# Vision_Impaired_Arduino_Board.net
KiCad netlist of a schematic drawn in EAGLE
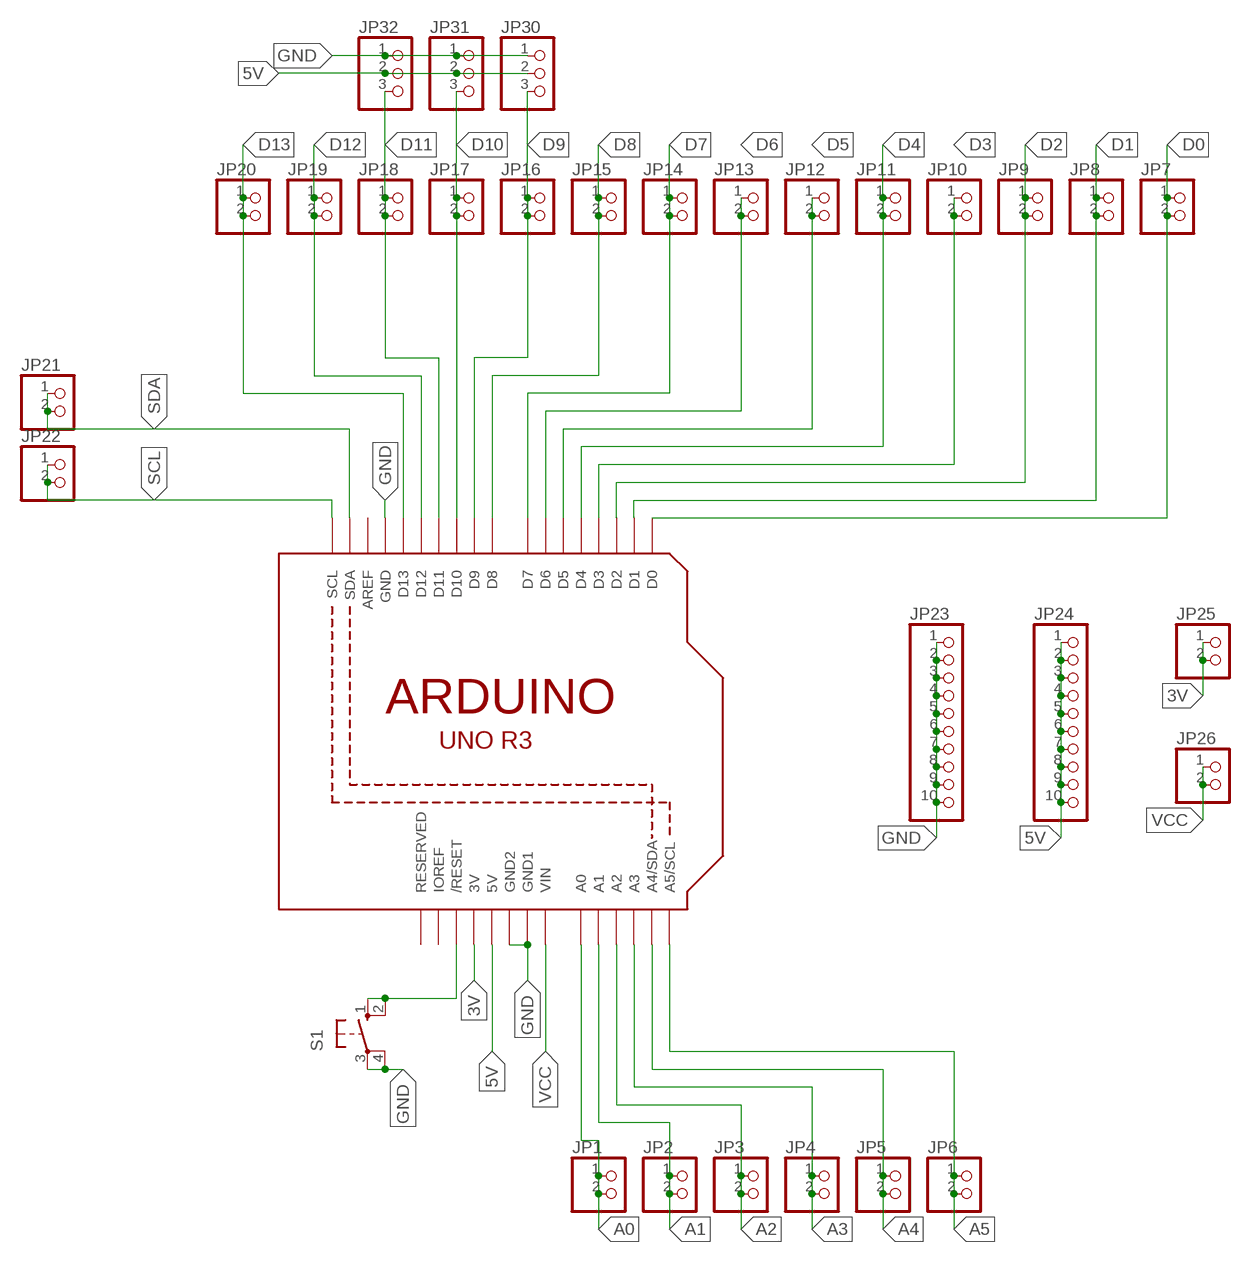
[diagram p0: schematic, sheet 1]

(export (version "E")
  (design (tool "Eeschema 10.0.6"))
  (components
    (comp (ref "JP1")
      (value "PINHD-1X2")
      (footprint "eagle-import:1X02")
      (libsource (lib "eagle-import") (part "PINHD-1X2"))
    )
    (comp (ref "JP2")
      (value "PINHD-1X2")
      (footprint "eagle-import:1X02")
      (libsource (lib "eagle-import") (part "PINHD-1X2"))
    )
    (comp (ref "JP3")
      (value "PINHD-1X2")
      (footprint "eagle-import:1X02")
      (libsource (lib "eagle-import") (part "PINHD-1X2"))
    )
    (comp (ref "JP4")
      (value "PINHD-1X2")
      (footprint "eagle-import:1X02")
      (libsource (lib "eagle-import") (part "PINHD-1X2"))
    )
    (comp (ref "JP5")
      (value "PINHD-1X2")
      (footprint "eagle-import:1X02")
      (libsource (lib "eagle-import") (part "PINHD-1X2"))
    )
    (comp (ref "JP6")
      (value "PINHD-1X2")
      (footprint "eagle-import:1X02")
      (libsource (lib "eagle-import") (part "PINHD-1X2"))
    )
    (comp (ref "JP7")
      (value "PINHD-1X2")
      (footprint "eagle-import:1X02")
      (libsource (lib "eagle-import") (part "PINHD-1X2"))
    )
    (comp (ref "JP8")
      (value "PINHD-1X2")
      (footprint "eagle-import:1X02")
      (libsource (lib "eagle-import") (part "PINHD-1X2"))
    )
    (comp (ref "JP9")
      (value "PINHD-1X2")
      (footprint "eagle-import:1X02")
      (libsource (lib "eagle-import") (part "PINHD-1X2"))
    )
    (comp (ref "JP10")
      (value "PINHD-1X2")
      (footprint "eagle-import:1X02")
      (libsource (lib "eagle-import") (part "PINHD-1X2"))
    )
    (comp (ref "JP11")
      (value "PINHD-1X2")
      (footprint "eagle-import:1X02")
      (libsource (lib "eagle-import") (part "PINHD-1X2"))
    )
    (comp (ref "JP12")
      (value "PINHD-1X2")
      (footprint "eagle-import:1X02")
      (libsource (lib "eagle-import") (part "PINHD-1X2"))
    )
    (comp (ref "JP13")
      (value "PINHD-1X2")
      (footprint "eagle-import:1X02")
      (libsource (lib "eagle-import") (part "PINHD-1X2"))
    )
    (comp (ref "JP14")
      (value "PINHD-1X2")
      (footprint "eagle-import:1X02")
      (libsource (lib "eagle-import") (part "PINHD-1X2"))
    )
    (comp (ref "JP15")
      (value "PINHD-1X2")
      (footprint "eagle-import:1X02")
      (libsource (lib "eagle-import") (part "PINHD-1X2"))
    )
    (comp (ref "JP16")
      (value "PINHD-1X2")
      (footprint "eagle-import:1X02")
      (libsource (lib "eagle-import") (part "PINHD-1X2"))
    )
    (comp (ref "JP17")
      (value "PINHD-1X2")
      (footprint "eagle-import:1X02")
      (libsource (lib "eagle-import") (part "PINHD-1X2"))
    )
    (comp (ref "JP18")
      (value "PINHD-1X2")
      (footprint "eagle-import:1X02")
      (libsource (lib "eagle-import") (part "PINHD-1X2"))
    )
    (comp (ref "JP19")
      (value "PINHD-1X2")
      (footprint "eagle-import:1X02")
      (libsource (lib "eagle-import") (part "PINHD-1X2"))
    )
    (comp (ref "JP20")
      (value "PINHD-1X2")
      (footprint "eagle-import:1X02")
      (libsource (lib "eagle-import") (part "PINHD-1X2"))
    )
    (comp (ref "JP21")
      (value "PINHD-1X2")
      (footprint "eagle-import:1X02")
      (libsource (lib "eagle-import") (part "PINHD-1X2"))
    )
    (comp (ref "JP22")
      (value "PINHD-1X2")
      (footprint "eagle-import:1X02")
      (libsource (lib "eagle-import") (part "PINHD-1X2"))
    )
    (comp (ref "JP23")
      (value "PINHD-1X10")
      (footprint "eagle-import:1X10")
      (libsource (lib "eagle-import") (part "PINHD-1X10"))
    )
    (comp (ref "JP24")
      (value "PINHD-1X10")
      (footprint "eagle-import:1X10")
      (libsource (lib "eagle-import") (part "PINHD-1X10"))
    )
    (comp (ref "JP25")
      (value "PINHD-1X2")
      (footprint "eagle-import:1X02")
      (libsource (lib "eagle-import") (part "PINHD-1X2"))
    )
    (comp (ref "JP26")
      (value "PINHD-1X2")
      (footprint "eagle-import:1X02")
      (libsource (lib "eagle-import") (part "PINHD-1X2"))
    )
    (comp (ref "JP30")
      (value "PINHD-1X3")
      (footprint "eagle-import:1X03")
      (libsource (lib "eagle-import") (part "PINHD-1X3"))
    )
    (comp (ref "JP31")
      (value "PINHD-1X3")
      (footprint "eagle-import:1X03")
      (libsource (lib "eagle-import") (part "PINHD-1X3"))
    )
    (comp (ref "JP32")
      (value "PINHD-1X3")
      (footprint "eagle-import:1X03")
      (libsource (lib "eagle-import") (part "PINHD-1X3"))
    )
    (comp (ref "S1")
      (value "40-XX")
      (footprint "eagle-import:B3F-40XX")
      (fields (field (name "MF") "OMRON COMPONENTS USA") (field (name "MPN") "B3F-4000"))
      (libsource (lib "eagle-import") (part "40-XX"))
    )
    (comp (ref "U1")
      (value "ARDUINOR3-BPLACE")
      (footprint "eagle-import:ARDUINOR3-BPLACE")
      (libsource (lib "eagle-import") (part "ARDUINOR3-BPLACE"))
    )
  )
  (nets
    (net (code "1") (name "3V") (class "Default")
      (node (ref "JP25") (pin "1") (pinfunction "1_1") (pintype "passive"))
      (node (ref "JP25") (pin "2") (pinfunction "2_2") (pintype "passive"))
      (node (ref "U1") (pin "3V") (pinfunction "3V_3V") (pintype "power_in"))
    )
    (net (code "2") (name "5V") (class "Default")
      (node (ref "JP24") (pin "1") (pinfunction "1_1") (pintype "passive"))
      (node (ref "JP24") (pin "10") (pinfunction "10_10") (pintype "passive"))
      (node (ref "JP24") (pin "2") (pinfunction "2_2") (pintype "passive"))
      (node (ref "JP24") (pin "3") (pinfunction "3_3") (pintype "passive"))
      (node (ref "JP24") (pin "4") (pinfunction "4_4") (pintype "passive"))
      (node (ref "JP24") (pin "5") (pinfunction "5_5") (pintype "passive"))
      (node (ref "JP24") (pin "6") (pinfunction "6_6") (pintype "passive"))
      (node (ref "JP24") (pin "7") (pinfunction "7_7") (pintype "passive"))
      (node (ref "JP24") (pin "8") (pinfunction "8_8") (pintype "passive"))
      (node (ref "JP24") (pin "9") (pinfunction "9_9") (pintype "passive"))
      (node (ref "JP30") (pin "2") (pinfunction "2_2") (pintype "passive"))
      (node (ref "JP31") (pin "2") (pinfunction "2_2") (pintype "passive"))
      (node (ref "JP32") (pin "2") (pinfunction "2_2") (pintype "passive"))
      (node (ref "U1") (pin "5V") (pinfunction "5V_5V") (pintype "power_in"))
    )
    (net (code "3") (name "A0") (class "Default")
      (node (ref "JP1") (pin "1") (pinfunction "1_1") (pintype "passive"))
      (node (ref "JP1") (pin "2") (pinfunction "2_2") (pintype "passive"))
      (node (ref "U1") (pin "A0") (pinfunction "A0_A0") (pintype "bidirectional"))
    )
    (net (code "4") (name "A1") (class "Default")
      (node (ref "JP2") (pin "1") (pinfunction "1_1") (pintype "passive"))
      (node (ref "JP2") (pin "2") (pinfunction "2_2") (pintype "passive"))
      (node (ref "U1") (pin "A1") (pinfunction "A1_A1") (pintype "bidirectional"))
    )
    (net (code "5") (name "A2") (class "Default")
      (node (ref "JP3") (pin "1") (pinfunction "1_1") (pintype "passive"))
      (node (ref "JP3") (pin "2") (pinfunction "2_2") (pintype "passive"))
      (node (ref "U1") (pin "A2") (pinfunction "A2_A2") (pintype "bidirectional"))
    )
    (net (code "6") (name "A3") (class "Default")
      (node (ref "JP4") (pin "1") (pinfunction "1_1") (pintype "passive"))
      (node (ref "JP4") (pin "2") (pinfunction "2_2") (pintype "passive"))
      (node (ref "U1") (pin "A3") (pinfunction "A3_A3") (pintype "bidirectional"))
    )
    (net (code "7") (name "A4") (class "Default")
      (node (ref "JP5") (pin "1") (pinfunction "1_1") (pintype "passive"))
      (node (ref "JP5") (pin "2") (pinfunction "2_2") (pintype "passive"))
      (node (ref "U1") (pin "A4") (pinfunction "A4/SDA_A4") (pintype "bidirectional"))
    )
    (net (code "8") (name "A5") (class "Default")
      (node (ref "JP6") (pin "1") (pinfunction "1_1") (pintype "passive"))
      (node (ref "JP6") (pin "2") (pinfunction "2_2") (pintype "passive"))
      (node (ref "U1") (pin "A5") (pinfunction "A5/SCL_A5") (pintype "bidirectional"))
    )
    (net (code "9") (name "D0") (class "Default")
      (node (ref "JP7") (pin "1") (pinfunction "1_1") (pintype "passive"))
      (node (ref "JP7") (pin "2") (pinfunction "2_2") (pintype "passive"))
      (node (ref "U1") (pin "D0") (pinfunction "D0_D0") (pintype "bidirectional"))
    )
    (net (code "10") (name "D1") (class "Default")
      (node (ref "JP8") (pin "1") (pinfunction "1_1") (pintype "passive"))
      (node (ref "JP8") (pin "2") (pinfunction "2_2") (pintype "passive"))
      (node (ref "U1") (pin "D1") (pinfunction "D1_D1") (pintype "bidirectional"))
    )
    (net (code "11") (name "D2") (class "Default")
      (node (ref "JP9") (pin "1") (pinfunction "1_1") (pintype "passive"))
      (node (ref "JP9") (pin "2") (pinfunction "2_2") (pintype "passive"))
      (node (ref "U1") (pin "D2") (pinfunction "D2_D2") (pintype "bidirectional"))
    )
    (net (code "12") (name "D3") (class "Default")
      (node (ref "JP10") (pin "1") (pinfunction "1_1") (pintype "passive"))
      (node (ref "JP10") (pin "2") (pinfunction "2_2") (pintype "passive"))
      (node (ref "U1") (pin "D3") (pinfunction "D3_D3") (pintype "bidirectional"))
    )
    (net (code "13") (name "D4") (class "Default")
      (node (ref "JP11") (pin "1") (pinfunction "1_1") (pintype "passive"))
      (node (ref "JP11") (pin "2") (pinfunction "2_2") (pintype "passive"))
      (node (ref "U1") (pin "D4") (pinfunction "D4_D4") (pintype "bidirectional"))
    )
    (net (code "14") (name "D5") (class "Default")
      (node (ref "JP12") (pin "1") (pinfunction "1_1") (pintype "passive"))
      (node (ref "JP12") (pin "2") (pinfunction "2_2") (pintype "passive"))
      (node (ref "U1") (pin "D5") (pinfunction "D5_D5") (pintype "bidirectional"))
    )
    (net (code "15") (name "D6") (class "Default")
      (node (ref "JP13") (pin "1") (pinfunction "1_1") (pintype "passive"))
      (node (ref "JP13") (pin "2") (pinfunction "2_2") (pintype "passive"))
      (node (ref "U1") (pin "D6") (pinfunction "D6_D6") (pintype "bidirectional"))
    )
    (net (code "16") (name "D7") (class "Default")
      (node (ref "JP14") (pin "1") (pinfunction "1_1") (pintype "passive"))
      (node (ref "JP14") (pin "2") (pinfunction "2_2") (pintype "passive"))
      (node (ref "U1") (pin "D7") (pinfunction "D7_D7") (pintype "bidirectional"))
    )
    (net (code "17") (name "D8") (class "Default")
      (node (ref "JP15") (pin "1") (pinfunction "1_1") (pintype "passive"))
      (node (ref "JP15") (pin "2") (pinfunction "2_2") (pintype "passive"))
      (node (ref "U1") (pin "D8") (pinfunction "D8_D8") (pintype "bidirectional"))
    )
    (net (code "18") (name "D9") (class "Default")
      (node (ref "JP16") (pin "1") (pinfunction "1_1") (pintype "passive"))
      (node (ref "JP16") (pin "2") (pinfunction "2_2") (pintype "passive"))
      (node (ref "JP30") (pin "3") (pinfunction "3_3") (pintype "passive"))
      (node (ref "U1") (pin "D9") (pinfunction "D9_D9") (pintype "bidirectional"))
    )
    (net (code "19") (name "D10") (class "Default")
      (node (ref "JP17") (pin "1") (pinfunction "1_1") (pintype "passive"))
      (node (ref "JP17") (pin "2") (pinfunction "2_2") (pintype "passive"))
      (node (ref "JP31") (pin "3") (pinfunction "3_3") (pintype "passive"))
      (node (ref "U1") (pin "D10") (pinfunction "D10_D10") (pintype "bidirectional"))
    )
    (net (code "20") (name "D11") (class "Default")
      (node (ref "JP18") (pin "1") (pinfunction "1_1") (pintype "passive"))
      (node (ref "JP18") (pin "2") (pinfunction "2_2") (pintype "passive"))
      (node (ref "JP32") (pin "3") (pinfunction "3_3") (pintype "passive"))
      (node (ref "U1") (pin "D11") (pinfunction "D11_D11") (pintype "bidirectional"))
    )
    (net (code "21") (name "D12") (class "Default")
      (node (ref "JP19") (pin "1") (pinfunction "1_1") (pintype "passive"))
      (node (ref "JP19") (pin "2") (pinfunction "2_2") (pintype "passive"))
      (node (ref "U1") (pin "D12") (pinfunction "D12_D12") (pintype "bidirectional"))
    )
    (net (code "22") (name "D13") (class "Default")
      (node (ref "JP20") (pin "1") (pinfunction "1_1") (pintype "passive"))
      (node (ref "JP20") (pin "2") (pinfunction "2_2") (pintype "passive"))
      (node (ref "U1") (pin "D13") (pinfunction "D13_D13") (pintype "bidirectional"))
    )
    (net (code "23") (name "GND") (class "Default")
      (node (ref "JP23") (pin "1") (pinfunction "1_1") (pintype "passive"))
      (node (ref "JP23") (pin "10") (pinfunction "10_10") (pintype "passive"))
      (node (ref "JP23") (pin "2") (pinfunction "2_2") (pintype "passive"))
      (node (ref "JP23") (pin "3") (pinfunction "3_3") (pintype "passive"))
      (node (ref "JP23") (pin "4") (pinfunction "4_4") (pintype "passive"))
      (node (ref "JP23") (pin "5") (pinfunction "5_5") (pintype "passive"))
      (node (ref "JP23") (pin "6") (pinfunction "6_6") (pintype "passive"))
      (node (ref "JP23") (pin "7") (pinfunction "7_7") (pintype "passive"))
      (node (ref "JP23") (pin "8") (pinfunction "8_8") (pintype "passive"))
      (node (ref "JP23") (pin "9") (pinfunction "9_9") (pintype "passive"))
      (node (ref "JP30") (pin "1") (pinfunction "1_1") (pintype "passive"))
      (node (ref "JP31") (pin "1") (pinfunction "1_1") (pintype "passive"))
      (node (ref "JP32") (pin "1") (pinfunction "1_1") (pintype "passive"))
      (node (ref "S1") (pin "3") (pinfunction "P_3") (pintype "passive"))
      (node (ref "S1") (pin "4") (pinfunction "P1_4") (pintype "passive"))
      (node (ref "U1") (pin "GND") (pinfunction "GND_GND") (pintype "power_in"))
      (node (ref "U1") (pin "GND1") (pinfunction "GND1_GND1") (pintype "power_in"))
      (node (ref "U1") (pin "GND2") (pinfunction "GND2_GND2") (pintype "power_in"))
    )
    (net (code "24") (name "Net-(S1-S)") (class "Default")
      (node (ref "S1") (pin "1") (pinfunction "S_1") (pintype "passive"))
      (node (ref "S1") (pin "2") (pinfunction "S1_2") (pintype "passive"))
      (node (ref "U1") (pin "RESET") (pinfunction "/RESET_RESET") (pintype "bidirectional"))
    )
    (net (code "25") (name "SCL") (class "Default")
      (node (ref "JP22") (pin "1") (pinfunction "1_1") (pintype "passive"))
      (node (ref "JP22") (pin "2") (pinfunction "2_2") (pintype "passive"))
      (node (ref "U1") (pin "SCL") (pinfunction "SCL_SCL") (pintype "bidirectional"))
    )
    (net (code "26") (name "SDA") (class "Default")
      (node (ref "JP21") (pin "1") (pinfunction "1_1") (pintype "passive"))
      (node (ref "JP21") (pin "2") (pinfunction "2_2") (pintype "passive"))
      (node (ref "U1") (pin "SDA") (pinfunction "SDA_SDA") (pintype "bidirectional"))
    )
    (net (code "27") (name "VCC") (class "Default")
      (node (ref "JP26") (pin "1") (pinfunction "1_1") (pintype "passive"))
      (node (ref "JP26") (pin "2") (pinfunction "2_2") (pintype "passive"))
      (node (ref "U1") (pin "VIN") (pinfunction "VIN_VIN") (pintype "power_in"))
    )
    (net (code "28") (name "unconnected-(U1-PadAREF)") (class "Default")
      (node (ref "U1") (pin "AREF") (pinfunction "AREF_AREF") (pintype "bidirectional"))
    )
    (net (code "29") (name "unconnected-(U1-PadIOREF)") (class "Default")
      (node (ref "U1") (pin "IOREF") (pinfunction "IOREF_IOREF") (pintype "output"))
    )
    (net (code "30") (name "unconnected-(U1-PadRESERVED)") (class "Default")
      (node (ref "U1") (pin "RESERVED") (pinfunction "RESERVED_RESERVED") (pintype "no_connect"))
    )
  )
)
